# SHEET_AVR-TEST.net
KiCad netlist of a schematic drawn in Altium Designer
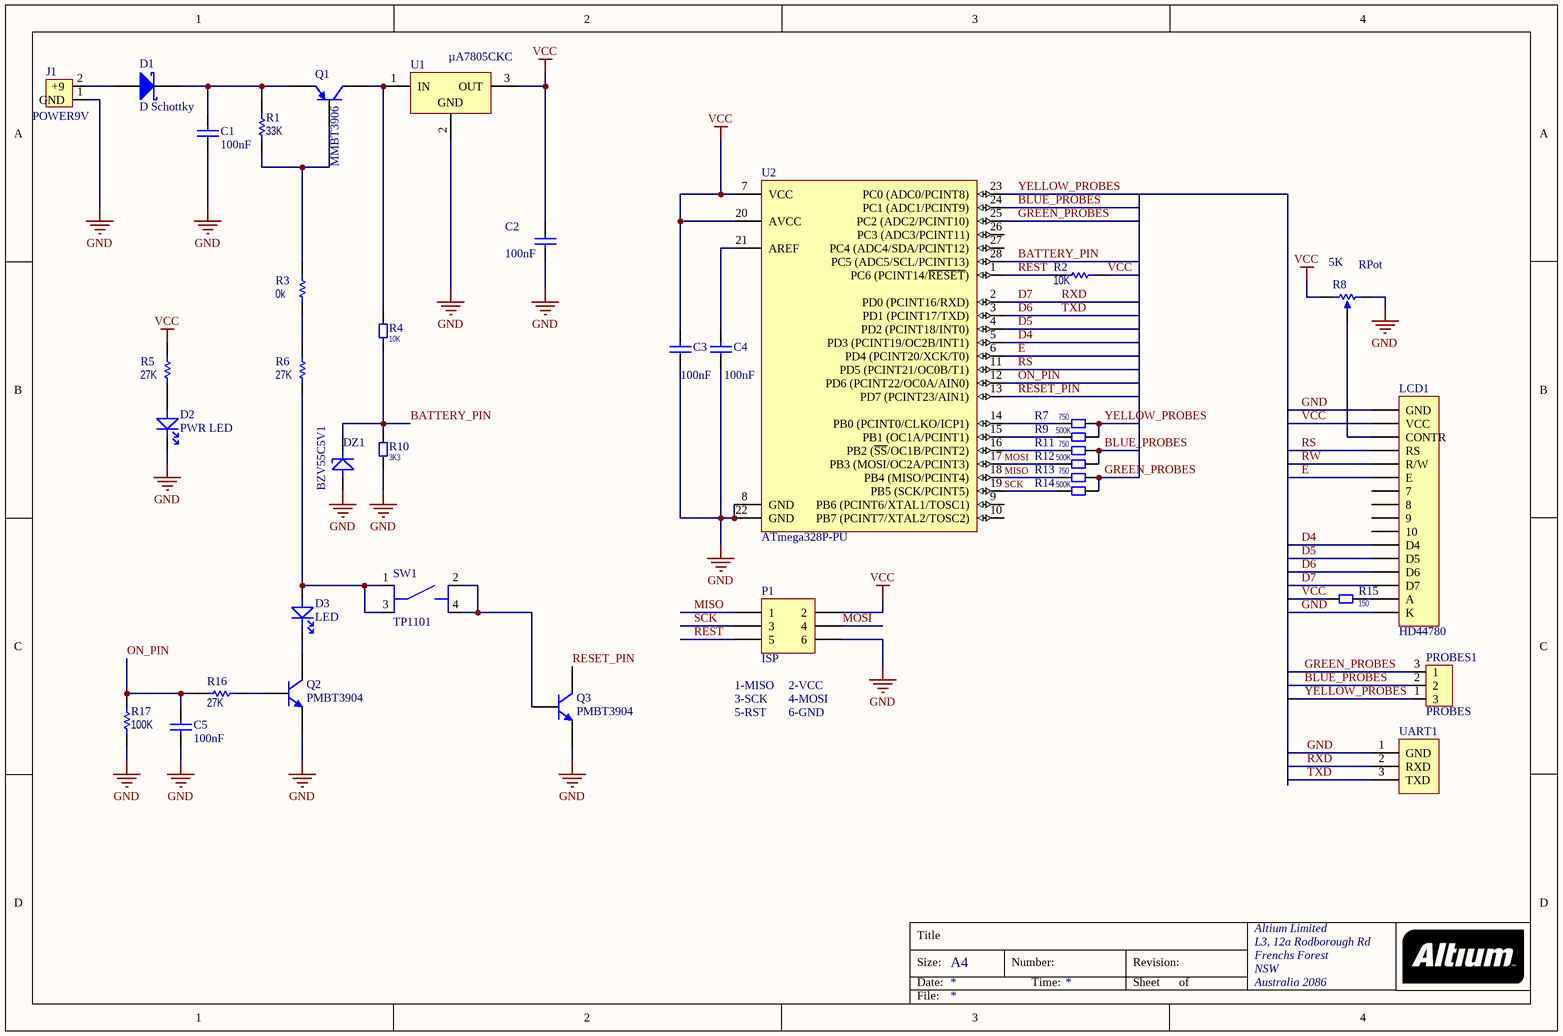
[diagram p0: SHEET_AVR-TEST.SchDoc]

(export (version "E")
  (design (tool "Eeschema 10.0.6"))
  (components
    (comp (ref "C1")
      (value "100nF")
      (footprint "C1206")
      (description "SMD Конденсатор 0805 NP0 25V")
      (fields (field (name "MFG") "kemet"))
      (libsource (lib "My_Int_Lib1") (part "CAP 0805 NP0"))
    )
    (comp (ref "C2")
      (value "100nF")
      (footprint "C1206")
      (description "SMD Конденсатор 0805 NP0 25V")
      (fields (field (name "MFG") "kemet"))
      (libsource (lib "My_Int_Lib1") (part "CAP 0805 NP0"))
    )
    (comp (ref "C3")
      (value "100nF")
      (footprint "C1206")
      (description "SMD Конденсатор 0805 NP0 25V")
      (fields (field (name "MFG") "kemet"))
      (libsource (lib "My_Int_Lib1") (part "CAP 0805 NP0"))
    )
    (comp (ref "C4")
      (value "100nF")
      (footprint "C1206")
      (description "SMD Конденсатор 0805 NP0 25V")
      (fields (field (name "MFG") "kemet"))
      (libsource (lib "My_Int_Lib1") (part "CAP 0805 NP0"))
    )
    (comp (ref "C5")
      (value "100nF")
      (footprint "C1206")
      (description "SMD Конденсатор 0805 NP0 25V")
      (fields (field (name "MFG") "kemet"))
      (libsource (lib "My_Int_Lib1") (part "CAP 0805 NP0"))
    )
    (comp (ref "D1")
      (value "D Schottky")
      (footprint "SMB")
      (description "Schottky Diode")
      (fields (field (name "PUBLISHER") "Altium Limited"))
      (libsource (lib "Miscellaneous Devices") (part "D Schottky"))
    )
    (comp (ref "D2") (value "PWR LED") (footprint "LED_254") (libsource (lib "My_Int_Lib1") (part "LED")))
    (comp (ref "D3") (value "LED") (footprint "LED_254") (libsource (lib "My_Int_Lib1") (part "LED")))
    (comp (ref "DZ1")
      (value "BZV55C5V1")
      (footprint "SOD80D")
      (description "SMD SILICON ZENER DIODE 0.5 WATT ± 5% TOLERANCE")
      (fields (field (name "MFG") "microsemi"))
      (libsource (lib "My_Int_Lib1") (part "DZ BZV55C5V1"))
    )
    (comp (ref "J1") (value "POWER9V") (footprint "TB2-5MM") (libsource (lib "My_Int_Lib1") (part "CON2")))
    (comp (ref "LCD1")
      (value "HD44780")
      (footprint "HDR1X16")
      (description "Header, 16-Pin")
      (fields (field (name "PUBLISHER") "Altium Limited"))
      (libsource (lib "Miscellaneous Connectors") (part "MHDR1X16"))
    )
    (comp (ref "P1")
      (value "ISP")
      (footprint "HDR2X3")
      (description "Header, 3-Pin, Dual row, Right Angle")
      (fields (field (name "PUBLISHER") "Altium Limited"))
      (libsource (lib "Miscellaneous Connectors") (part "Header 3X2H"))
    )
    (comp (ref "PROBES1")
      (value "PROBES")
      (footprint "TB3-5MM")
      (description "Клемник на плату пр мой шаг5мм")
      (fields (field (name "PARTNUMBER") "TBN050-D10-03 (TB-03)") (field (name "MFG") "MoreThanAll"))
      (libsource (lib "My_Int_Lib1") (part "CON TBN050-D10-03"))
    )
    (comp (ref "Q1")
      (value "MMBT3906")
      (footprint "SOT23_N")
      (description "PNP Switching Transistor")
      (fields (field (name "PUBLISHER") "Altium Limited"))
      (libsource (lib "Philips Discrete BJT - Low Power") (part "MMBT3906"))
    )
    (comp (ref "Q2")
      (value "PMBT3904")
      (footprint "SOT23_N")
      (description "NPN Switching Transistor")
      (fields (field (name "PUBLISHER") "Altium Limited"))
      (libsource (lib "Philips Discrete BJT - Low Power") (part "PMBT3904"))
    )
    (comp (ref "Q3")
      (value "PMBT3904")
      (footprint "SOT23_N")
      (description "NPN Switching Transistor")
      (fields (field (name "PUBLISHER") "Altium Limited"))
      (libsource (lib "Philips Discrete BJT - Low Power") (part "PMBT3904"))
    )
    (comp (ref "R1")
      (value "33K")
      (footprint "R0805")
      (description "Flat Chip Fuse Resistor, 0.47 Ohm to 10 Ohm Range, 5% Tolerance, 0805 Size, 0.1 W")
      (fields (field (name "Comment") "ERQF06") (field (name "PUBLISHER") "Altium Limited"))
      (libsource (lib "Panasonic Resistor") (part "ERQF06"))
    )
    (comp (ref "R2")
      (value "10K")
      (footprint "RC0805DS")
      (description "Flat Chip Fuse Resistor, 0.47 Ohm to 10 Ohm Range, 5% Tolerance, 0805 Size, 0.1 W")
      (fields (field (name "Comment") "ERQF06") (field (name "PUBLISHER") "Altium Limited"))
      (libsource (lib "Panasonic Resistor") (part "ERQF06"))
    )
    (comp (ref "R3")
      (value "0k")
      (footprint "R0805")
      (description "Flat Chip Fuse Resistor, 0.47 Ohm to 10 Ohm Range, 5% Tolerance, 0805 Size, 0.1 W")
      (fields (field (name "Comment") "ERQF06") (field (name "PUBLISHER") "Altium Limited"))
      (libsource (lib "Panasonic Resistor") (part "ERQF06"))
    )
    (comp (ref "R4")
      (value "10K")
      (footprint "R0805")
      (description "SMD Резистор 0805")
      (libsource (lib "My_Int_Lib1") (part "RES 0805"))
    )
    (comp (ref "R5")
      (value "27K")
      (footprint "r0805")
      (description "Flat Chip Fuse Resistor, 0.47 Ohm to 10 Ohm Range, 5% Tolerance, 0805 Size, 0.1 W")
      (fields (field (name "Comment") "ERQF06") (field (name "PUBLISHER") "Altium Limited"))
      (libsource (lib "Panasonic Resistor") (part "ERQF06"))
    )
    (comp (ref "R6")
      (value "27K")
      (footprint "R0805")
      (description "Flat Chip Fuse Resistor, 0.47 Ohm to 10 Ohm Range, 5% Tolerance, 0805 Size, 0.1 W")
      (fields (field (name "Comment") "ERQF06") (field (name "PUBLISHER") "Altium Limited"))
      (libsource (lib "Panasonic Resistor") (part "ERQF06"))
    )
    (comp (ref "R7")
      (value "750")
      (footprint "R0805")
      (description "SMD Резистор 0805")
      (libsource (lib "My_Int_Lib1") (part "RES 0805"))
    )
    (comp (ref "R8")
      (value "RPot")
      (footprint "VR5")
      (description "Potentiometer")
      (fields (field (name "ALTIUM_VALUE") "5K") (field (name "PUBLISHER") "Altium Limited"))
      (libsource (lib "Miscellaneous Devices") (part "RPot"))
    )
    (comp (ref "R9")
      (value "500K")
      (footprint "R0805")
      (description "SMD Резистор 0805")
      (libsource (lib "My_Int_Lib1") (part "RES 0805"))
    )
    (comp (ref "R10")
      (value "3K3")
      (footprint "R0805")
      (description "SMD Резистор 0805")
      (libsource (lib "My_Int_Lib1") (part "RES 0805"))
    )
    (comp (ref "R11")
      (value "750")
      (footprint "R0805")
      (description "SMD Резистор 0805")
      (libsource (lib "My_Int_Lib1") (part "RES 0805"))
    )
    (comp (ref "R12")
      (value "500K")
      (footprint "R0805")
      (description "SMD Резистор 0805")
      (libsource (lib "My_Int_Lib1") (part "RES 0805"))
    )
    (comp (ref "R13")
      (value "750")
      (footprint "R0805")
      (description "SMD Резистор 0805")
      (libsource (lib "My_Int_Lib1") (part "RES 0805"))
    )
    (comp (ref "R14")
      (value "500K")
      (footprint "R0805")
      (description "SMD Резистор 0805")
      (libsource (lib "My_Int_Lib1") (part "RES 0805"))
    )
    (comp (ref "R15")
      (value "150")
      (footprint "R0805")
      (description "SMD Резистор 0805")
      (libsource (lib "My_Int_Lib1") (part "RES 0805"))
    )
    (comp (ref "R16")
      (value "27K")
      (footprint "R0805")
      (description "Flat Chip Fuse Resistor, 0.47 Ohm to 10 Ohm Range, 5% Tolerance, 0805 Size, 0.1 W")
      (fields (field (name "Comment") "ERQF06") (field (name "PUBLISHER") "Altium Limited"))
      (libsource (lib "Panasonic Resistor") (part "ERQF06"))
    )
    (comp (ref "R17")
      (value "100K")
      (footprint "R0805")
      (description "Flat Chip Fuse Resistor, 0.47 Ohm to 10 Ohm Range, 5% Tolerance, 0805 Size, 0.1 W")
      (fields (field (name "Comment") "ERQF06") (field (name "PUBLISHER") "Altium Limited"))
      (libsource (lib "Panasonic Resistor") (part "ERQF06"))
    )
    (comp (ref "SW1")
      (value "TP1101")
      (footprint "SW TP1101")
      (description "Кнопка")
      (fields (field (name "MFG") "amegatech"))
      (libsource (lib "My_Int_Lib1") (part "SW TP1101"))
    )
    (comp (ref "U1")
      (value "µA7805CKC")
      (footprint "TO-92")
      (description "Positive-Voltage Regulator")
      (fields (field (name "PUBLISHER") "Altium Limited"))
      (libsource (lib "TI Power Mgt Voltage Regulator") (part "µA7805CKC"))
    )
    (comp (ref "U2")
      (value "ATmega328P-PU")
      (footprint "28P3")
      (fields (field (name "PUBLISHER") "Altium Limited"))
      (libsource (lib "Atmel Microcontroller 8-Bit megaAVR") (part "ATmega328P-PU"))
    )
    (comp (ref "UART1")
      (value "Header 3")
      (footprint "HDR1X3")
      (description "Header, 3-Pin")
      (fields (field (name "PUBLISHER") "Altium Limited"))
      (libsource (lib "Miscellaneous Connectors") (part "Header 3"))
    )
  )
  (nets
    (net (code "1") (name "/BATTERY_PIN") (class "Default")
      (node (ref "DZ1") (pin "2") (pinfunction "2_2") (pintype "passive"))
      (node (ref "R10") (pin "1") (pinfunction "1_1") (pintype "passive"))
      (node (ref "R4") (pin "2") (pinfunction "2_2") (pintype "passive"))
      (node (ref "U2") (pin "28") (pinfunction "PC5_(ADC5/SCL/PCINT13)_28") (pintype "bidirectional"))
    )
    (net (code "2") (name "/BLUE_PROBES") (class "Default")
      (node (ref "PROBES1") (pin "2") (pinfunction "2_2") (pintype "passive"))
      (node (ref "R11") (pin "2") (pinfunction "2_2") (pintype "passive"))
      (node (ref "R12") (pin "2") (pinfunction "2_2") (pintype "passive"))
      (node (ref "U2") (pin "24") (pinfunction "PC1_(ADC1/PCINT9)_24") (pintype "bidirectional"))
    )
    (net (code "3") (name "/D4") (class "Default")
      (node (ref "LCD1") (pin "11") (pinfunction "D4_11") (pintype "passive"))
      (node (ref "U2") (pin "5") (pinfunction "PD3_(PCINT19/OC2B/INT1)_5") (pintype "bidirectional"))
    )
    (net (code "4") (name "/D5") (class "Default")
      (node (ref "LCD1") (pin "12") (pinfunction "D5_12") (pintype "passive"))
      (node (ref "U2") (pin "4") (pinfunction "PD2_(PCINT18/INT0)_4") (pintype "bidirectional"))
    )
    (net (code "5") (name "/D6") (class "Default")
      (node (ref "LCD1") (pin "13") (pinfunction "D6_13") (pintype "passive"))
      (node (ref "U2") (pin "3") (pinfunction "PD1_(PCINT17/TXD)_3") (pintype "bidirectional"))
      (node (ref "UART1") (pin "3") (pinfunction "TXD_3") (pintype "passive"))
    )
    (net (code "6") (name "/D7") (class "Default")
      (node (ref "LCD1") (pin "14") (pinfunction "D7_14") (pintype "passive"))
      (node (ref "U2") (pin "2") (pinfunction "PD0_(PCINT16/RXD)_2") (pintype "bidirectional"))
      (node (ref "UART1") (pin "2") (pinfunction "RXD_2") (pintype "passive"))
    )
    (net (code "7") (name "/E") (class "Default")
      (node (ref "LCD1") (pin "6") (pinfunction "E_6") (pintype "passive"))
      (node (ref "U2") (pin "6") (pinfunction "PD4_(PCINT20/XCK/T0)_6") (pintype "bidirectional"))
    )
    (net (code "8") (name "/GREEN_PROBES") (class "Default")
      (node (ref "PROBES1") (pin "3") (pinfunction "1_3") (pintype "passive"))
      (node (ref "R13") (pin "2") (pinfunction "2_2") (pintype "passive"))
      (node (ref "R14") (pin "2") (pinfunction "2_2") (pintype "passive"))
      (node (ref "U2") (pin "25") (pinfunction "PC2_(ADC2/PCINT10)_25") (pintype "bidirectional"))
    )
    (net (code "9") (name "/MISO") (class "Default")
      (node (ref "P1") (pin "1") (pinfunction "1_1") (pintype "passive"))
      (node (ref "R13") (pin "1") (pinfunction "1_1") (pintype "passive"))
      (node (ref "U2") (pin "18") (pinfunction "PB4_(MISO/PCINT4)_18") (pintype "bidirectional"))
    )
    (net (code "10") (name "/MOSI") (class "Default")
      (node (ref "P1") (pin "4") (pinfunction "4_4") (pintype "passive"))
      (node (ref "R12") (pin "1") (pinfunction "1_1") (pintype "passive"))
      (node (ref "U2") (pin "17") (pinfunction "PB3_(MOSI/OC2A/PCINT3)_17") (pintype "bidirectional"))
    )
    (net (code "11") (name "/ON_PIN") (class "Default")
      (node (ref "C5") (pin "2") (pinfunction "2_2") (pintype "passive"))
      (node (ref "R16") (pin "2") (pinfunction "2_2") (pintype "passive"))
      (node (ref "R17") (pin "2") (pinfunction "2_2") (pintype "passive"))
      (node (ref "U2") (pin "12") (pinfunction "PD6_(PCINT22/OC0A/AIN0)_12") (pintype "bidirectional"))
    )
    (net (code "12") (name "/RESET_PIN") (class "Default")
      (node (ref "Q3") (pin "3") (pinfunction "C_3") (pintype "passive"))
      (node (ref "U2") (pin "13") (pinfunction "PD7_(PCINT23/AIN1)_13") (pintype "bidirectional"))
    )
    (net (code "13") (name "/REST") (class "Default")
      (node (ref "P1") (pin "5") (pinfunction "5_5") (pintype "passive"))
      (node (ref "R2") (pin "2") (pinfunction "2_2") (pintype "passive"))
      (node (ref "U2") (pin "1") (pinfunction "PC6_(PCINT14/~{RESET})_1") (pintype "bidirectional"))
    )
    (net (code "14") (name "/RS") (class "Default")
      (node (ref "LCD1") (pin "4") (pinfunction "RS_4") (pintype "passive"))
      (node (ref "U2") (pin "11") (pinfunction "PD5_(PCINT21/OC0B/T1)_11") (pintype "bidirectional"))
    )
    (net (code "15") (name "/RW") (class "Default")
      (node (ref "LCD1") (pin "5") (pinfunction "R/W_5") (pintype "passive"))
    )
    (net (code "16") (name "/SCK") (class "Default")
      (node (ref "P1") (pin "3") (pinfunction "3_3") (pintype "passive"))
      (node (ref "R14") (pin "1") (pinfunction "1_1") (pintype "passive"))
      (node (ref "U2") (pin "19") (pinfunction "PB5_(SCK/PCINT5)_19") (pintype "bidirectional"))
    )
    (net (code "17") (name "/YELLOW_PROBES") (class "Default")
      (node (ref "PROBES1") (pin "1") (pinfunction "3_1") (pintype "passive"))
      (node (ref "R7") (pin "2") (pinfunction "2_2") (pintype "passive"))
      (node (ref "R9") (pin "2") (pinfunction "2_2") (pintype "passive"))
      (node (ref "U2") (pin "23") (pinfunction "PC0_(ADC0/PCINT8)_23") (pintype "bidirectional"))
    )
    (net (code "18") (name "GND") (class "Default")
      (node (ref "C1") (pin "1") (pinfunction "1_1") (pintype "passive"))
      (node (ref "C2") (pin "1") (pinfunction "1_1") (pintype "passive"))
      (node (ref "C3") (pin "1") (pinfunction "1_1") (pintype "passive"))
      (node (ref "C4") (pin "1") (pinfunction "1_1") (pintype "passive"))
      (node (ref "C5") (pin "1") (pinfunction "1_1") (pintype "passive"))
      (node (ref "D2") (pin "2") (pinfunction "2_2") (pintype "passive"))
      (node (ref "DZ1") (pin "1") (pinfunction "1_1") (pintype "passive"))
      (node (ref "J1") (pin "1") (pinfunction "GND_1") (pintype "passive"))
      (node (ref "LCD1") (pin "1") (pinfunction "GND_1") (pintype "passive"))
      (node (ref "LCD1") (pin "16") (pinfunction "K_16") (pintype "passive"))
      (node (ref "P1") (pin "6") (pinfunction "6_6") (pintype "passive"))
      (node (ref "Q2") (pin "2") (pinfunction "E_2") (pintype "passive"))
      (node (ref "Q3") (pin "2") (pinfunction "E_2") (pintype "passive"))
      (node (ref "R10") (pin "2") (pinfunction "2_2") (pintype "passive"))
      (node (ref "R17") (pin "1") (pinfunction "1_1") (pintype "passive"))
      (node (ref "R8") (pin "2") (pinfunction "BOT_2") (pintype "passive"))
      (node (ref "U1") (pin "2") (pinfunction "GND_2") (pintype "power_in"))
      (node (ref "U2") (pin "22") (pinfunction "GND_22") (pintype "power_in"))
      (node (ref "U2") (pin "8") (pinfunction "GND_8") (pintype "power_in"))
      (node (ref "UART1") (pin "1") (pinfunction "GND_1") (pintype "passive"))
    )
    (net (code "19") (name "Net-(D1-A)") (class "Default")
      (node (ref "D1") (pin "1") (pinfunction "A_1") (pintype "passive"))
      (node (ref "J1") (pin "2") (pinfunction "+9_2") (pintype "passive"))
    )
    (net (code "20") (name "Net-(D1-K)") (class "Default")
      (node (ref "C1") (pin "2") (pinfunction "2_2") (pintype "passive"))
      (node (ref "D1") (pin "2") (pinfunction "K_2") (pintype "passive"))
      (node (ref "Q1") (pin "2") (pinfunction "E_2") (pintype "passive"))
      (node (ref "R1") (pin "2") (pinfunction "2_2") (pintype "passive"))
    )
    (net (code "21") (name "Net-(D2-Pad1)") (class "Default")
      (node (ref "D2") (pin "1") (pinfunction "1_1") (pintype "passive"))
      (node (ref "R5") (pin "1") (pinfunction "1_1") (pintype "passive"))
    )
    (net (code "22") (name "Net-(D3-Pad1)") (class "Default")
      (node (ref "D3") (pin "1") (pinfunction "1_1") (pintype "passive"))
      (node (ref "R6") (pin "1") (pinfunction "1_1") (pintype "passive"))
      (node (ref "SW1") (pin "1") (pinfunction "1_1") (pintype "passive"))
      (node (ref "SW1") (pin "3") (pinfunction "3_3") (pintype "passive"))
    )
    (net (code "23") (name "Net-(LCD1-A)") (class "Default")
      (node (ref "LCD1") (pin "15") (pinfunction "A_15") (pintype "passive"))
      (node (ref "R15") (pin "2") (pinfunction "2_2") (pintype "passive"))
    )
    (net (code "24") (name "Net-(LCD1-CONTR)") (class "Default")
      (node (ref "LCD1") (pin "3") (pinfunction "CONTR_3") (pintype "passive"))
      (node (ref "R8") (pin "3") (pinfunction "TAP_3") (pintype "passive"))
    )
    (net (code "25") (name "Net-(Q1-B)") (class "Default")
      (node (ref "Q1") (pin "1") (pinfunction "B_1") (pintype "passive"))
      (node (ref "R1") (pin "1") (pinfunction "1_1") (pintype "passive"))
      (node (ref "R3") (pin "2") (pinfunction "2_2") (pintype "passive"))
    )
    (net (code "26") (name "Net-(Q1-C)") (class "Default")
      (node (ref "Q1") (pin "3") (pinfunction "C_3") (pintype "passive"))
      (node (ref "R4") (pin "1") (pinfunction "1_1") (pintype "passive"))
      (node (ref "U1") (pin "1") (pinfunction "IN_1") (pintype "power_in"))
    )
    (net (code "27") (name "Net-(Q2-B)") (class "Default")
      (node (ref "Q2") (pin "1") (pinfunction "B_1") (pintype "passive"))
      (node (ref "R16") (pin "1") (pinfunction "1_1") (pintype "passive"))
    )
    (net (code "28") (name "Net-(Q2-C)") (class "Default")
      (node (ref "D3") (pin "2") (pinfunction "2_2") (pintype "passive"))
      (node (ref "Q2") (pin "3") (pinfunction "C_3") (pintype "passive"))
    )
    (net (code "29") (name "Net-(Q3-B)") (class "Default")
      (node (ref "Q3") (pin "1") (pinfunction "B_1") (pintype "passive"))
      (node (ref "SW1") (pin "2") (pinfunction "2_2") (pintype "passive"))
      (node (ref "SW1") (pin "4") (pinfunction "4_4") (pintype "passive"))
    )
    (net (code "30") (name "Net-(R3-Pad1)") (class "Default")
      (node (ref "R3") (pin "1") (pinfunction "1_1") (pintype "passive"))
      (node (ref "R6") (pin "2") (pinfunction "2_2") (pintype "passive"))
    )
    (net (code "31") (name "Net-(U2-AREF)") (class "Default")
      (node (ref "C4") (pin "2") (pinfunction "2_2") (pintype "passive"))
      (node (ref "U2") (pin "21") (pinfunction "AREF_21") (pintype "power_in"))
    )
    (net (code "32") (name "Net-(U2-PB0_(PCINT0{slash}CLKO{slash}ICP1))") (class "Default")
      (node (ref "R7") (pin "1") (pinfunction "1_1") (pintype "passive"))
      (node (ref "U2") (pin "14") (pinfunction "PB0_(PCINT0/CLKO/ICP1)_14") (pintype "bidirectional"))
    )
    (net (code "33") (name "Net-(U2-PB1_(OC1A{slash}PCINT1))") (class "Default")
      (node (ref "R9") (pin "1") (pinfunction "1_1") (pintype "passive"))
      (node (ref "U2") (pin "15") (pinfunction "PB1_(OC1A/PCINT1)_15") (pintype "bidirectional"))
    )
    (net (code "34") (name "Net-(U2-PB2_(~{SS}{slash}OC1B{slash}PCINT2))") (class "Default")
      (node (ref "R11") (pin "1") (pinfunction "1_1") (pintype "passive"))
      (node (ref "U2") (pin "16") (pinfunction "PB2_(~{SS}/OC1B/PCINT2)_16") (pintype "bidirectional"))
    )
    (net (code "35") (name "VCC") (class "Default")
      (node (ref "C2") (pin "2") (pinfunction "2_2") (pintype "passive"))
      (node (ref "C3") (pin "2") (pinfunction "2_2") (pintype "passive"))
      (node (ref "LCD1") (pin "2") (pinfunction "VCC_2") (pintype "passive"))
      (node (ref "P1") (pin "2") (pinfunction "2_2") (pintype "passive"))
      (node (ref "R15") (pin "1") (pinfunction "1_1") (pintype "passive"))
      (node (ref "R2") (pin "1") (pinfunction "1_1") (pintype "passive"))
      (node (ref "R5") (pin "2") (pinfunction "2_2") (pintype "passive"))
      (node (ref "R8") (pin "1") (pinfunction "TOP_1") (pintype "passive"))
      (node (ref "U1") (pin "3") (pinfunction "OUT_3") (pintype "power_in"))
      (node (ref "U2") (pin "20") (pinfunction "AVCC_20") (pintype "power_in"))
      (node (ref "U2") (pin "7") (pinfunction "VCC_7") (pintype "power_in"))
    )
    (net (code "36") (name "unconnected-(LCD1-Pad7)") (class "Default")
      (node (ref "LCD1") (pin "7") (pinfunction "7_7") (pintype "passive"))
    )
    (net (code "37") (name "unconnected-(LCD1-Pad8)") (class "Default")
      (node (ref "LCD1") (pin "8") (pinfunction "8_8") (pintype "passive"))
    )
    (net (code "38") (name "unconnected-(LCD1-Pad9)") (class "Default")
      (node (ref "LCD1") (pin "9") (pinfunction "9_9") (pintype "passive"))
    )
    (net (code "39") (name "unconnected-(LCD1-Pad10)") (class "Default")
      (node (ref "LCD1") (pin "10") (pinfunction "10_10") (pintype "passive"))
    )
    (net (code "40") (name "unconnected-(U2-PB6_(PCINT6{slash}XTAL1{slash}TOSC1)-Pad9)") (class "Default")
      (node (ref "U2") (pin "9") (pinfunction "PB6_(PCINT6/XTAL1/TOSC1)_9") (pintype "bidirectional"))
    )
    (net (code "41") (name "unconnected-(U2-PB7_(PCINT7{slash}XTAL2{slash}TOSC2)-Pad10)") (class "Default")
      (node (ref "U2") (pin "10") (pinfunction "PB7_(PCINT7/XTAL2/TOSC2)_10") (pintype "bidirectional"))
    )
    (net (code "42") (name "unconnected-(U2-PC3_(ADC3{slash}PCINT11)-Pad26)") (class "Default")
      (node (ref "U2") (pin "26") (pinfunction "PC3_(ADC3/PCINT11)_26") (pintype "bidirectional"))
    )
    (net (code "43") (name "unconnected-(U2-PC4_(ADC4{slash}SDA{slash}PCINT12)-Pad27)") (class "Default")
      (node (ref "U2") (pin "27") (pinfunction "PC4_(ADC4/SDA/PCINT12)_27") (pintype "bidirectional"))
    )
  )
)
